# l298_updated_cap.net
KiCad netlist of a schematic drawn in EAGLE
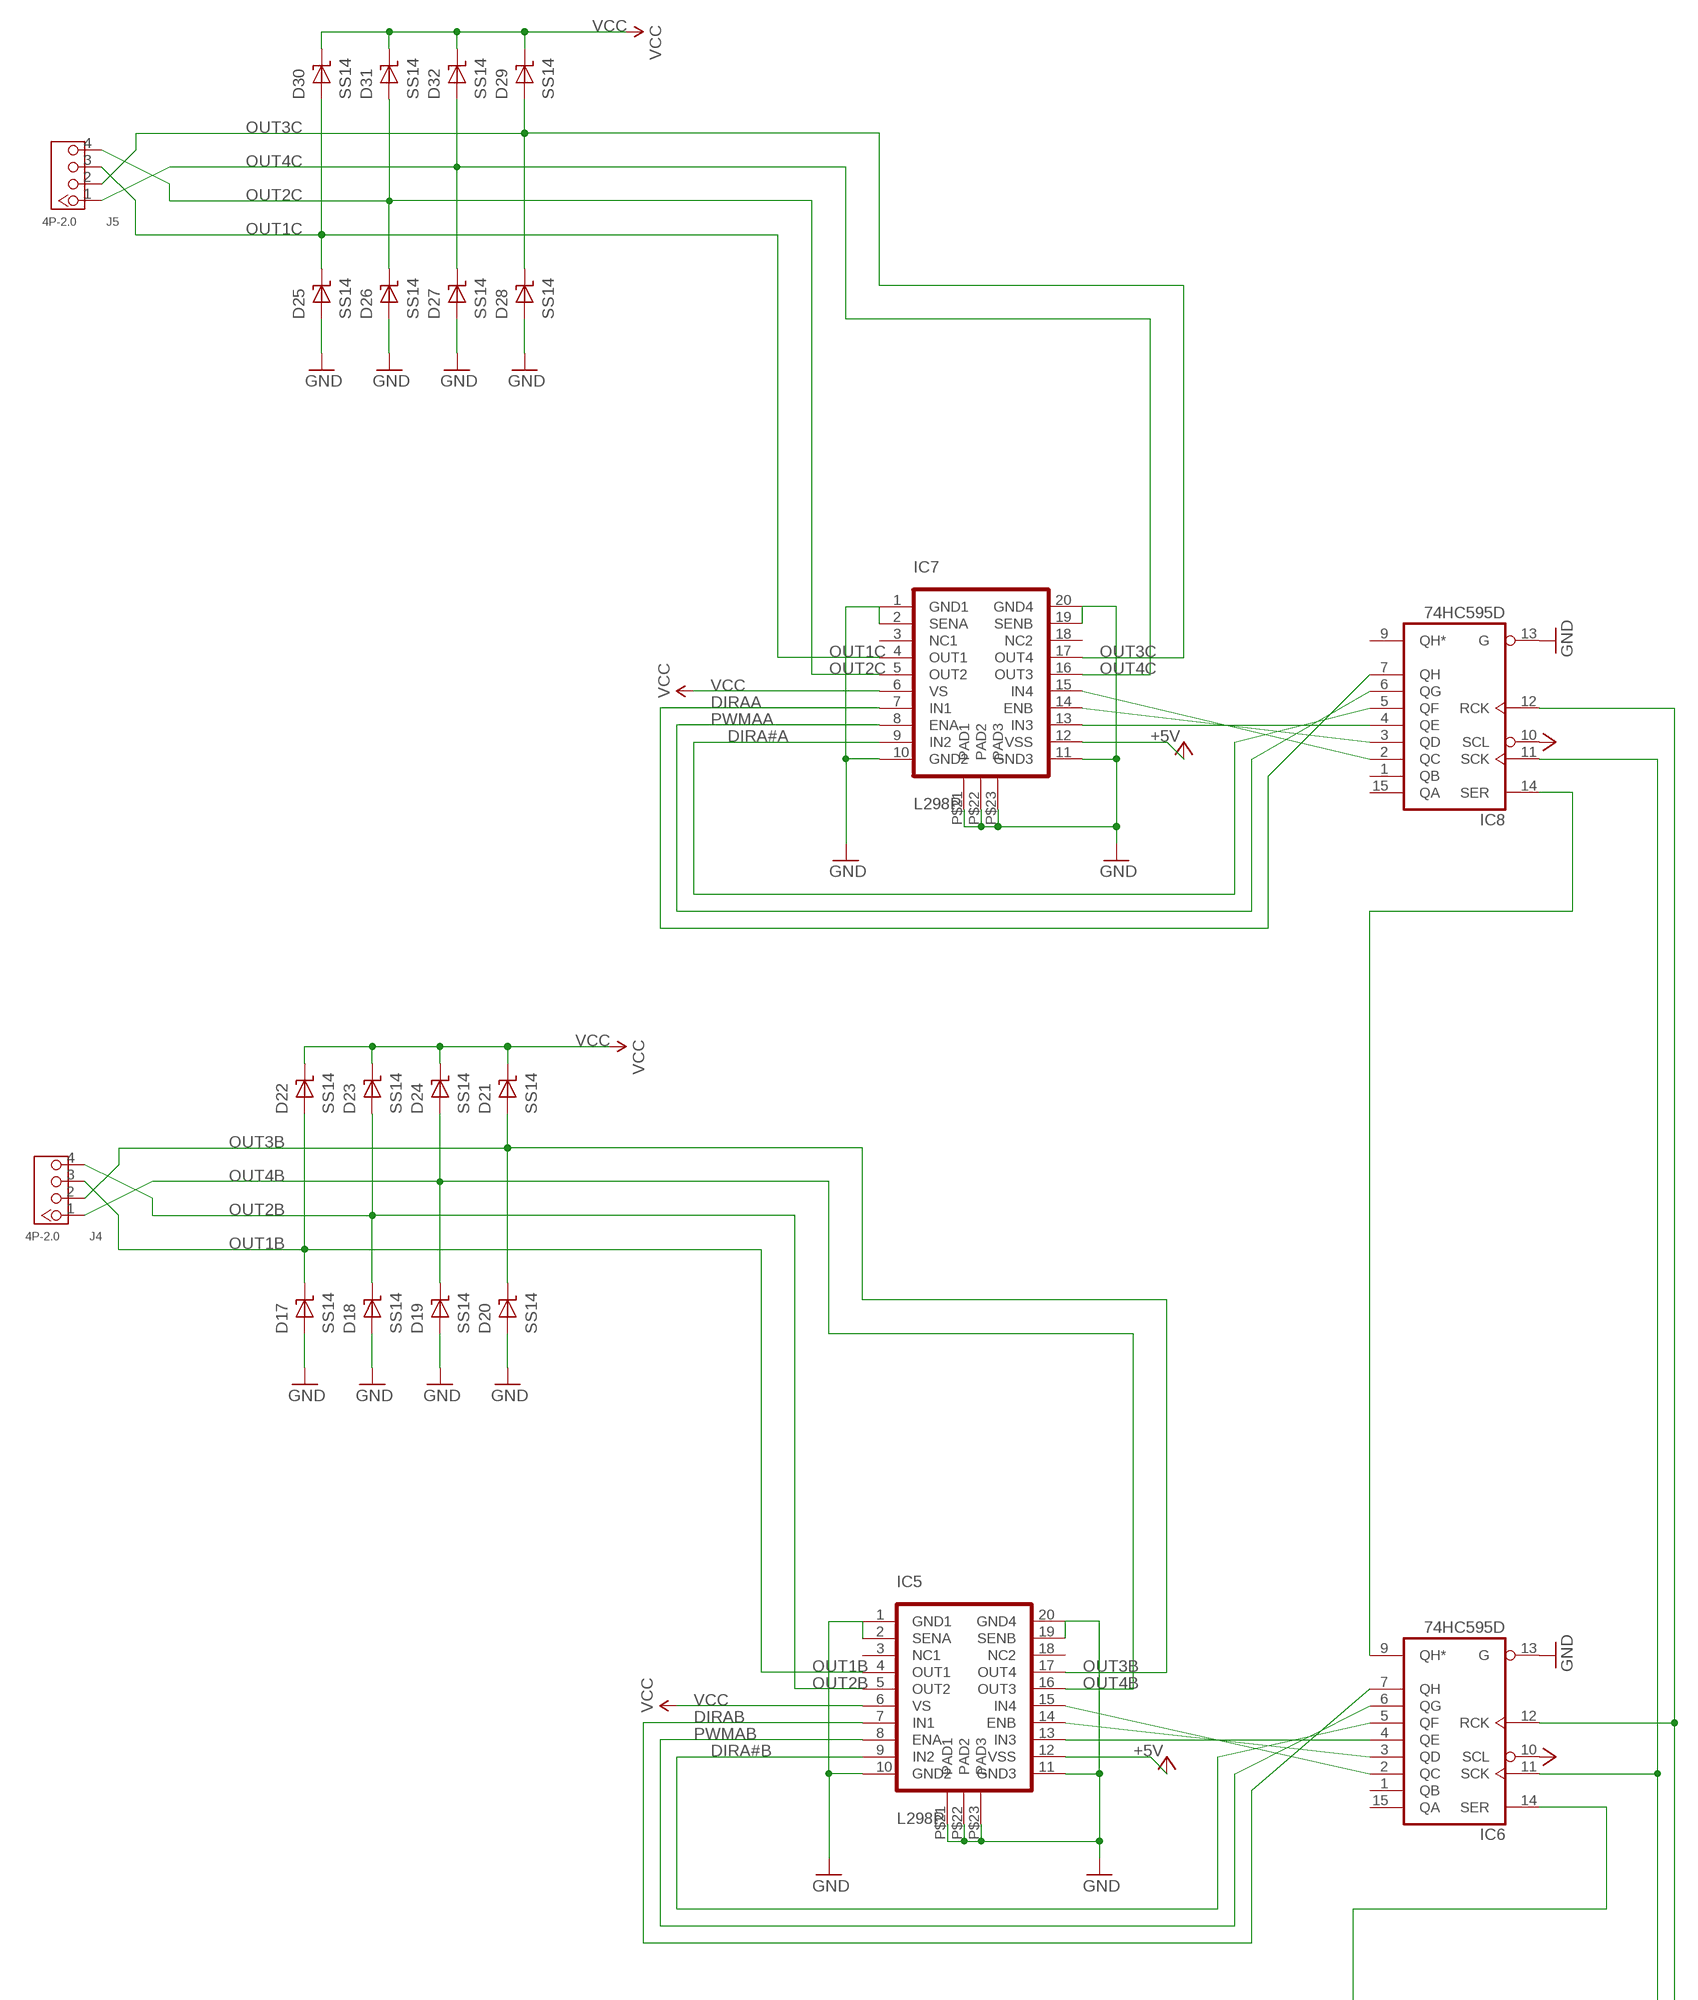
[diagram p0: schematic, sheet 1, part 1 of 2]
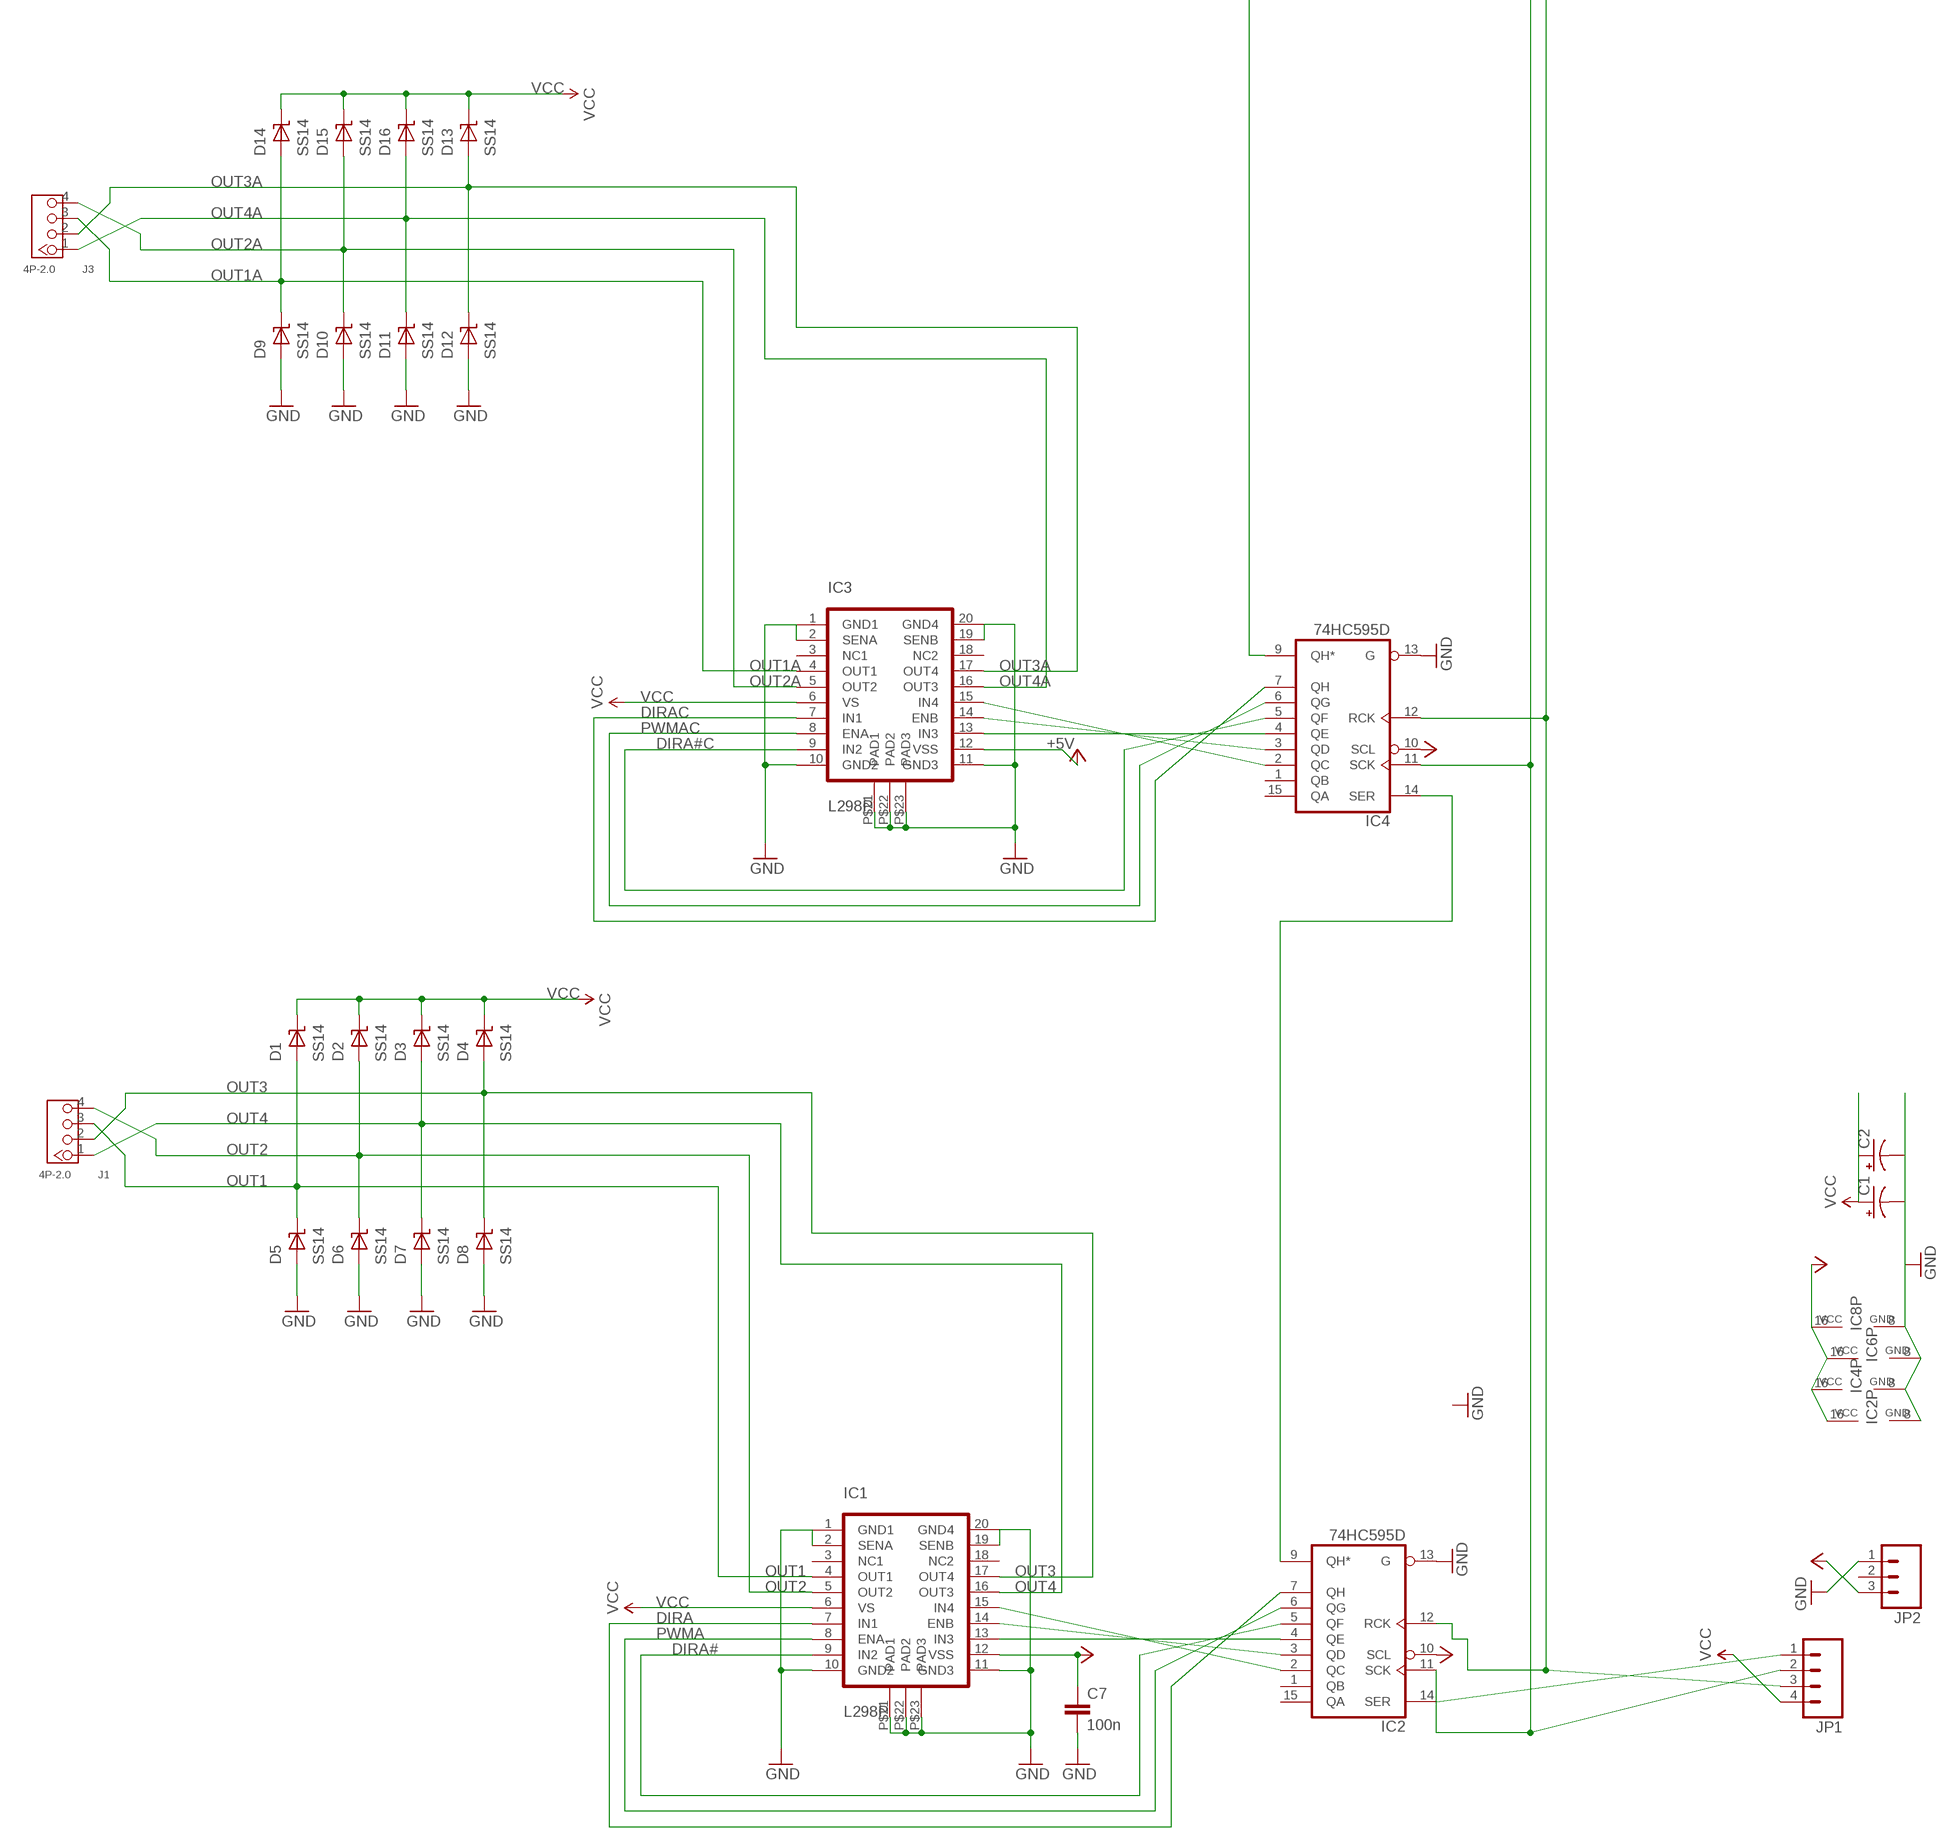
[diagram p1: schematic, sheet 1, part 2 of 2]

(export (version "E")
  (design (tool "Eeschema 10.0.6"))
  (components
    (comp (ref "C1")
      (value "CAP_POL1206")
      (footprint "eagle-import:EIA3216")
      (libsource (lib "eagle-import") (part "CAP_POL1206"))
    )
    (comp (ref "C2")
      (value "CAP_POL3528")
      (footprint "eagle-import:EIA3528")
      (libsource (lib "eagle-import") (part "CAP_POL3528"))
    )
    (comp (ref "C7")
      (value "100n")
      (footprint "eagle-import:C0603-ROUND")
      (libsource (lib "eagle-import") (part "C-EUC0603"))
    )
    (comp (ref "D1")
      (value "SS14")
      (footprint "eagle-import:SMA")
      (libsource (lib "eagle-import") (part "SS14"))
    )
    (comp (ref "D2")
      (value "SS14")
      (footprint "eagle-import:SMA")
      (libsource (lib "eagle-import") (part "SS14"))
    )
    (comp (ref "D3")
      (value "SS14")
      (footprint "eagle-import:SMA")
      (libsource (lib "eagle-import") (part "SS14"))
    )
    (comp (ref "D4")
      (value "SS14")
      (footprint "eagle-import:SMA")
      (libsource (lib "eagle-import") (part "SS14"))
    )
    (comp (ref "D5")
      (value "SS14")
      (footprint "eagle-import:SMA")
      (libsource (lib "eagle-import") (part "SS14"))
    )
    (comp (ref "D6")
      (value "SS14")
      (footprint "eagle-import:SMA")
      (libsource (lib "eagle-import") (part "SS14"))
    )
    (comp (ref "D7")
      (value "SS14")
      (footprint "eagle-import:SMA")
      (libsource (lib "eagle-import") (part "SS14"))
    )
    (comp (ref "D8")
      (value "SS14")
      (footprint "eagle-import:SMA")
      (libsource (lib "eagle-import") (part "SS14"))
    )
    (comp (ref "D9")
      (value "SS14")
      (footprint "eagle-import:SMA")
      (libsource (lib "eagle-import") (part "SS14"))
    )
    (comp (ref "D10")
      (value "SS14")
      (footprint "eagle-import:SMA")
      (libsource (lib "eagle-import") (part "SS14"))
    )
    (comp (ref "D11")
      (value "SS14")
      (footprint "eagle-import:SMA")
      (libsource (lib "eagle-import") (part "SS14"))
    )
    (comp (ref "D12")
      (value "SS14")
      (footprint "eagle-import:SMA")
      (libsource (lib "eagle-import") (part "SS14"))
    )
    (comp (ref "D13")
      (value "SS14")
      (footprint "eagle-import:SMA")
      (libsource (lib "eagle-import") (part "SS14"))
    )
    (comp (ref "D14")
      (value "SS14")
      (footprint "eagle-import:SMA")
      (libsource (lib "eagle-import") (part "SS14"))
    )
    (comp (ref "D15")
      (value "SS14")
      (footprint "eagle-import:SMA")
      (libsource (lib "eagle-import") (part "SS14"))
    )
    (comp (ref "D16")
      (value "SS14")
      (footprint "eagle-import:SMA")
      (libsource (lib "eagle-import") (part "SS14"))
    )
    (comp (ref "D17")
      (value "SS14")
      (footprint "eagle-import:SMA")
      (libsource (lib "eagle-import") (part "SS14"))
    )
    (comp (ref "D18")
      (value "SS14")
      (footprint "eagle-import:SMA")
      (libsource (lib "eagle-import") (part "SS14"))
    )
    (comp (ref "D19")
      (value "SS14")
      (footprint "eagle-import:SMA")
      (libsource (lib "eagle-import") (part "SS14"))
    )
    (comp (ref "D20")
      (value "SS14")
      (footprint "eagle-import:SMA")
      (libsource (lib "eagle-import") (part "SS14"))
    )
    (comp (ref "D21")
      (value "SS14")
      (footprint "eagle-import:SMA")
      (libsource (lib "eagle-import") (part "SS14"))
    )
    (comp (ref "D22")
      (value "SS14")
      (footprint "eagle-import:SMA")
      (libsource (lib "eagle-import") (part "SS14"))
    )
    (comp (ref "D23")
      (value "SS14")
      (footprint "eagle-import:SMA")
      (libsource (lib "eagle-import") (part "SS14"))
    )
    (comp (ref "D24")
      (value "SS14")
      (footprint "eagle-import:SMA")
      (libsource (lib "eagle-import") (part "SS14"))
    )
    (comp (ref "D25")
      (value "SS14")
      (footprint "eagle-import:SMA")
      (libsource (lib "eagle-import") (part "SS14"))
    )
    (comp (ref "D26")
      (value "SS14")
      (footprint "eagle-import:SMA")
      (libsource (lib "eagle-import") (part "SS14"))
    )
    (comp (ref "D27")
      (value "SS14")
      (footprint "eagle-import:SMA")
      (libsource (lib "eagle-import") (part "SS14"))
    )
    (comp (ref "D28")
      (value "SS14")
      (footprint "eagle-import:SMA")
      (libsource (lib "eagle-import") (part "SS14"))
    )
    (comp (ref "D29")
      (value "SS14")
      (footprint "eagle-import:SMA")
      (libsource (lib "eagle-import") (part "SS14"))
    )
    (comp (ref "D30")
      (value "SS14")
      (footprint "eagle-import:SMA")
      (libsource (lib "eagle-import") (part "SS14"))
    )
    (comp (ref "D31")
      (value "SS14")
      (footprint "eagle-import:SMA")
      (libsource (lib "eagle-import") (part "SS14"))
    )
    (comp (ref "D32")
      (value "SS14")
      (footprint "eagle-import:SMA")
      (libsource (lib "eagle-import") (part "SS14"))
    )
    (comp (ref "IC1")
      (value "L298P")
      (footprint "eagle-import:POWER-SO20")
      (libsource (lib "eagle-import") (part "L298P"))
    )
    (comp (ref "IC2")
      (value "74HC595D")
      (footprint "eagle-import:SO16")
      (libsource (lib "eagle-import") (part "74595DHC"))
    )
    (comp (ref "IC3")
      (value "L298P")
      (footprint "eagle-import:POWER-SO20")
      (libsource (lib "eagle-import") (part "L298P"))
    )
    (comp (ref "IC4")
      (value "74HC595D")
      (footprint "eagle-import:SO16")
      (libsource (lib "eagle-import") (part "74595DHC"))
    )
    (comp (ref "IC5")
      (value "L298P")
      (footprint "eagle-import:POWER-SO20")
      (libsource (lib "eagle-import") (part "L298P"))
    )
    (comp (ref "IC6")
      (value "74HC595D")
      (footprint "eagle-import:SO16")
      (libsource (lib "eagle-import") (part "74595DHC"))
    )
    (comp (ref "IC7")
      (value "L298P")
      (footprint "eagle-import:POWER-SO20")
      (libsource (lib "eagle-import") (part "L298P"))
    )
    (comp (ref "IC8")
      (value "74HC595D")
      (footprint "eagle-import:SO16")
      (libsource (lib "eagle-import") (part "74595DHC"))
    )
    (comp (ref "J1")
      (value "4P-2.0")
      (footprint "eagle-import:HW4-2.0")
      (libsource (lib "eagle-import") (part "GROVE-CONNECTOR-DIP(4P-2.0)"))
    )
    (comp (ref "J3")
      (value "4P-2.0")
      (footprint "eagle-import:HW4-2.0")
      (libsource (lib "eagle-import") (part "GROVE-CONNECTOR-DIP(4P-2.0)"))
    )
    (comp (ref "J4")
      (value "4P-2.0")
      (footprint "eagle-import:HW4-2.0")
      (libsource (lib "eagle-import") (part "GROVE-CONNECTOR-DIP(4P-2.0)"))
    )
    (comp (ref "J5")
      (value "4P-2.0")
      (footprint "eagle-import:HW4-2.0")
      (libsource (lib "eagle-import") (part "GROVE-CONNECTOR-DIP(4P-2.0)"))
    )
    (comp (ref "JP1")
      (value "M04PTH")
      (footprint "eagle-import:1X04")
      (libsource (lib "eagle-import") (part "M04PTH"))
    )
    (comp (ref "JP2")
      (value "M03PTH")
      (footprint "eagle-import:1X03")
      (libsource (lib "eagle-import") (part "M03PTH"))
    )
  )
  (nets
    (net (code "1") (name "+5V") (class "Default")
      (node (ref "C7") (pin "1") (pinfunction "1_1") (pintype "passive"))
      (node (ref "IC1") (pin "P$12") (pinfunction "VSS_P$12") (pintype "power_in"))
      (node (ref "IC2") (pin "10") (pinfunction "SCL_10") (pintype "input"))
      (node (ref "IC2") (pin "16") (pinfunction "VCC_16") (pintype "power_in"))
      (node (ref "IC3") (pin "P$12") (pinfunction "VSS_P$12") (pintype "power_in"))
      (node (ref "IC4") (pin "10") (pinfunction "SCL_10") (pintype "input"))
      (node (ref "IC4") (pin "16") (pinfunction "VCC_16") (pintype "power_in"))
      (node (ref "IC5") (pin "P$12") (pinfunction "VSS_P$12") (pintype "power_in"))
      (node (ref "IC6") (pin "10") (pinfunction "SCL_10") (pintype "input"))
      (node (ref "IC6") (pin "16") (pinfunction "VCC_16") (pintype "power_in"))
      (node (ref "IC7") (pin "P$12") (pinfunction "VSS_P$12") (pintype "power_in"))
      (node (ref "IC8") (pin "10") (pinfunction "SCL_10") (pintype "input"))
      (node (ref "IC8") (pin "16") (pinfunction "VCC_16") (pintype "power_in"))
      (node (ref "JP2") (pin "3") (pinfunction "3_3") (pintype "passive"))
    )
    (net (code "2") (name "/DIRA") (class "Default")
      (node (ref "IC1") (pin "P$7") (pinfunction "IN1_P$7") (pintype "input"))
      (node (ref "IC2") (pin "7") (pinfunction "QH_7") (pintype "tri_state"))
    )
    (net (code "3") (name "/DIRA#") (class "Default")
      (node (ref "IC1") (pin "P$9") (pinfunction "IN2_P$9") (pintype "input"))
      (node (ref "IC2") (pin "5") (pinfunction "QF_5") (pintype "tri_state"))
    )
    (net (code "4") (name "/DIRA#A") (class "Default")
      (node (ref "IC7") (pin "P$9") (pinfunction "IN2_P$9") (pintype "input"))
      (node (ref "IC8") (pin "5") (pinfunction "QF_5") (pintype "tri_state"))
    )
    (net (code "5") (name "/DIRA#B") (class "Default")
      (node (ref "IC5") (pin "P$9") (pinfunction "IN2_P$9") (pintype "input"))
      (node (ref "IC6") (pin "5") (pinfunction "QF_5") (pintype "tri_state"))
    )
    (net (code "6") (name "/DIRA#C") (class "Default")
      (node (ref "IC3") (pin "P$9") (pinfunction "IN2_P$9") (pintype "input"))
      (node (ref "IC4") (pin "5") (pinfunction "QF_5") (pintype "tri_state"))
    )
    (net (code "7") (name "/DIRAA") (class "Default")
      (node (ref "IC7") (pin "P$7") (pinfunction "IN1_P$7") (pintype "input"))
      (node (ref "IC8") (pin "7") (pinfunction "QH_7") (pintype "tri_state"))
    )
    (net (code "8") (name "/DIRAB") (class "Default")
      (node (ref "IC5") (pin "P$7") (pinfunction "IN1_P$7") (pintype "input"))
      (node (ref "IC6") (pin "7") (pinfunction "QH_7") (pintype "tri_state"))
    )
    (net (code "9") (name "/DIRAC") (class "Default")
      (node (ref "IC3") (pin "P$7") (pinfunction "IN1_P$7") (pintype "input"))
      (node (ref "IC4") (pin "7") (pinfunction "QH_7") (pintype "tri_state"))
    )
    (net (code "10") (name "/OUT1") (class "Default")
      (node (ref "D1") (pin "P$2") (pinfunction "A_P$2") (pintype "bidirectional"))
      (node (ref "D5") (pin "P$1") (pinfunction "K_P$1") (pintype "bidirectional"))
      (node (ref "IC1") (pin "P$4") (pinfunction "OUT1_P$4") (pintype "output"))
      (node (ref "J1") (pin "3") (pinfunction "3_3") (pintype "bidirectional"))
    )
    (net (code "11") (name "/OUT1A") (class "Default")
      (node (ref "D14") (pin "P$2") (pinfunction "A_P$2") (pintype "bidirectional"))
      (node (ref "D9") (pin "P$1") (pinfunction "K_P$1") (pintype "bidirectional"))
      (node (ref "IC3") (pin "P$4") (pinfunction "OUT1_P$4") (pintype "output"))
      (node (ref "J3") (pin "3") (pinfunction "3_3") (pintype "bidirectional"))
    )
    (net (code "12") (name "/OUT1B") (class "Default")
      (node (ref "D17") (pin "P$1") (pinfunction "K_P$1") (pintype "bidirectional"))
      (node (ref "D22") (pin "P$2") (pinfunction "A_P$2") (pintype "bidirectional"))
      (node (ref "IC5") (pin "P$4") (pinfunction "OUT1_P$4") (pintype "output"))
      (node (ref "J4") (pin "3") (pinfunction "3_3") (pintype "bidirectional"))
    )
    (net (code "13") (name "/OUT1C") (class "Default")
      (node (ref "D25") (pin "P$1") (pinfunction "K_P$1") (pintype "bidirectional"))
      (node (ref "D30") (pin "P$2") (pinfunction "A_P$2") (pintype "bidirectional"))
      (node (ref "IC7") (pin "P$4") (pinfunction "OUT1_P$4") (pintype "output"))
      (node (ref "J5") (pin "3") (pinfunction "3_3") (pintype "bidirectional"))
    )
    (net (code "14") (name "/OUT2") (class "Default")
      (node (ref "D2") (pin "P$2") (pinfunction "A_P$2") (pintype "bidirectional"))
      (node (ref "D6") (pin "P$1") (pinfunction "K_P$1") (pintype "bidirectional"))
      (node (ref "IC1") (pin "P$5") (pinfunction "OUT2_P$5") (pintype "output"))
      (node (ref "J1") (pin "4") (pinfunction "4_4") (pintype "bidirectional"))
    )
    (net (code "15") (name "/OUT2A") (class "Default")
      (node (ref "D10") (pin "P$1") (pinfunction "K_P$1") (pintype "bidirectional"))
      (node (ref "D15") (pin "P$2") (pinfunction "A_P$2") (pintype "bidirectional"))
      (node (ref "IC3") (pin "P$5") (pinfunction "OUT2_P$5") (pintype "output"))
      (node (ref "J3") (pin "4") (pinfunction "4_4") (pintype "bidirectional"))
    )
    (net (code "16") (name "/OUT2B") (class "Default")
      (node (ref "D18") (pin "P$1") (pinfunction "K_P$1") (pintype "bidirectional"))
      (node (ref "D23") (pin "P$2") (pinfunction "A_P$2") (pintype "bidirectional"))
      (node (ref "IC5") (pin "P$5") (pinfunction "OUT2_P$5") (pintype "output"))
      (node (ref "J4") (pin "4") (pinfunction "4_4") (pintype "bidirectional"))
    )
    (net (code "17") (name "/OUT2C") (class "Default")
      (node (ref "D26") (pin "P$1") (pinfunction "K_P$1") (pintype "bidirectional"))
      (node (ref "D31") (pin "P$2") (pinfunction "A_P$2") (pintype "bidirectional"))
      (node (ref "IC7") (pin "P$5") (pinfunction "OUT2_P$5") (pintype "output"))
      (node (ref "J5") (pin "4") (pinfunction "4_4") (pintype "bidirectional"))
    )
    (net (code "18") (name "/OUT3") (class "Default")
      (node (ref "D4") (pin "P$2") (pinfunction "A_P$2") (pintype "bidirectional"))
      (node (ref "D8") (pin "P$1") (pinfunction "K_P$1") (pintype "bidirectional"))
      (node (ref "IC1") (pin "P$17") (pinfunction "OUT4_P$17") (pintype "output"))
      (node (ref "J1") (pin "2") (pinfunction "2_2") (pintype "bidirectional"))
    )
    (net (code "19") (name "/OUT3A") (class "Default")
      (node (ref "D12") (pin "P$1") (pinfunction "K_P$1") (pintype "bidirectional"))
      (node (ref "D13") (pin "P$2") (pinfunction "A_P$2") (pintype "bidirectional"))
      (node (ref "IC3") (pin "P$17") (pinfunction "OUT4_P$17") (pintype "output"))
      (node (ref "J3") (pin "2") (pinfunction "2_2") (pintype "bidirectional"))
    )
    (net (code "20") (name "/OUT3B") (class "Default")
      (node (ref "D20") (pin "P$1") (pinfunction "K_P$1") (pintype "bidirectional"))
      (node (ref "D21") (pin "P$2") (pinfunction "A_P$2") (pintype "bidirectional"))
      (node (ref "IC5") (pin "P$17") (pinfunction "OUT4_P$17") (pintype "output"))
      (node (ref "J4") (pin "2") (pinfunction "2_2") (pintype "bidirectional"))
    )
    (net (code "21") (name "/OUT3C") (class "Default")
      (node (ref "D28") (pin "P$1") (pinfunction "K_P$1") (pintype "bidirectional"))
      (node (ref "D29") (pin "P$2") (pinfunction "A_P$2") (pintype "bidirectional"))
      (node (ref "IC7") (pin "P$17") (pinfunction "OUT4_P$17") (pintype "output"))
      (node (ref "J5") (pin "2") (pinfunction "2_2") (pintype "bidirectional"))
    )
    (net (code "22") (name "/OUT4") (class "Default")
      (node (ref "D3") (pin "P$2") (pinfunction "A_P$2") (pintype "bidirectional"))
      (node (ref "D7") (pin "P$1") (pinfunction "K_P$1") (pintype "bidirectional"))
      (node (ref "IC1") (pin "P$16") (pinfunction "OUT3_P$16") (pintype "output"))
      (node (ref "J1") (pin "1") (pinfunction "1_1") (pintype "bidirectional"))
    )
    (net (code "23") (name "/OUT4A") (class "Default")
      (node (ref "D11") (pin "P$1") (pinfunction "K_P$1") (pintype "bidirectional"))
      (node (ref "D16") (pin "P$2") (pinfunction "A_P$2") (pintype "bidirectional"))
      (node (ref "IC3") (pin "P$16") (pinfunction "OUT3_P$16") (pintype "output"))
      (node (ref "J3") (pin "1") (pinfunction "1_1") (pintype "bidirectional"))
    )
    (net (code "24") (name "/OUT4B") (class "Default")
      (node (ref "D19") (pin "P$1") (pinfunction "K_P$1") (pintype "bidirectional"))
      (node (ref "D24") (pin "P$2") (pinfunction "A_P$2") (pintype "bidirectional"))
      (node (ref "IC5") (pin "P$16") (pinfunction "OUT3_P$16") (pintype "output"))
      (node (ref "J4") (pin "1") (pinfunction "1_1") (pintype "bidirectional"))
    )
    (net (code "25") (name "/OUT4C") (class "Default")
      (node (ref "D27") (pin "P$1") (pinfunction "K_P$1") (pintype "bidirectional"))
      (node (ref "D32") (pin "P$2") (pinfunction "A_P$2") (pintype "bidirectional"))
      (node (ref "IC7") (pin "P$16") (pinfunction "OUT3_P$16") (pintype "output"))
      (node (ref "J5") (pin "1") (pinfunction "1_1") (pintype "bidirectional"))
    )
    (net (code "26") (name "/PWMA") (class "Default")
      (node (ref "IC1") (pin "P$8") (pinfunction "ENA_P$8") (pintype "input"))
      (node (ref "IC2") (pin "6") (pinfunction "QG_6") (pintype "tri_state"))
    )
    (net (code "27") (name "/PWMAA") (class "Default")
      (node (ref "IC7") (pin "P$8") (pinfunction "ENA_P$8") (pintype "input"))
      (node (ref "IC8") (pin "6") (pinfunction "QG_6") (pintype "tri_state"))
    )
    (net (code "28") (name "/PWMAB") (class "Default")
      (node (ref "IC5") (pin "P$8") (pinfunction "ENA_P$8") (pintype "input"))
      (node (ref "IC6") (pin "6") (pinfunction "QG_6") (pintype "tri_state"))
    )
    (net (code "29") (name "/PWMAC") (class "Default")
      (node (ref "IC3") (pin "P$8") (pinfunction "ENA_P$8") (pintype "input"))
      (node (ref "IC4") (pin "6") (pinfunction "QG_6") (pintype "tri_state"))
    )
    (net (code "30") (name "GND") (class "Default")
      (node (ref "C1") (pin "C") (pinfunction "-_C") (pintype "passive"))
      (node (ref "C2") (pin "C") (pinfunction "-_C") (pintype "passive"))
      (node (ref "C7") (pin "2") (pinfunction "2_2") (pintype "passive"))
      (node (ref "D10") (pin "P$2") (pinfunction "A_P$2") (pintype "bidirectional"))
      (node (ref "D11") (pin "P$2") (pinfunction "A_P$2") (pintype "bidirectional"))
      (node (ref "D12") (pin "P$2") (pinfunction "A_P$2") (pintype "bidirectional"))
      (node (ref "D17") (pin "P$2") (pinfunction "A_P$2") (pintype "bidirectional"))
      (node (ref "D18") (pin "P$2") (pinfunction "A_P$2") (pintype "bidirectional"))
      (node (ref "D19") (pin "P$2") (pinfunction "A_P$2") (pintype "bidirectional"))
      (node (ref "D20") (pin "P$2") (pinfunction "A_P$2") (pintype "bidirectional"))
      (node (ref "D25") (pin "P$2") (pinfunction "A_P$2") (pintype "bidirectional"))
      (node (ref "D26") (pin "P$2") (pinfunction "A_P$2") (pintype "bidirectional"))
      (node (ref "D27") (pin "P$2") (pinfunction "A_P$2") (pintype "bidirectional"))
      (node (ref "D28") (pin "P$2") (pinfunction "A_P$2") (pintype "bidirectional"))
      (node (ref "D5") (pin "P$2") (pinfunction "A_P$2") (pintype "bidirectional"))
      (node (ref "D6") (pin "P$2") (pinfunction "A_P$2") (pintype "bidirectional"))
      (node (ref "D7") (pin "P$2") (pinfunction "A_P$2") (pintype "bidirectional"))
      (node (ref "D8") (pin "P$2") (pinfunction "A_P$2") (pintype "bidirectional"))
      (node (ref "D9") (pin "P$2") (pinfunction "A_P$2") (pintype "bidirectional"))
      (node (ref "IC1") (pin "P$1") (pinfunction "GND1_P$1") (pintype "power_in"))
      (node (ref "IC1") (pin "P$10") (pinfunction "GND2_P$10") (pintype "power_in"))
      (node (ref "IC1") (pin "P$11") (pinfunction "GND3_P$11") (pintype "power_in"))
      (node (ref "IC1") (pin "P$19") (pinfunction "SENB_P$19") (pintype "input"))
      (node (ref "IC1") (pin "P$2") (pinfunction "SENA_P$2") (pintype "input"))
      (node (ref "IC1") (pin "P$20") (pinfunction "GND4_P$20") (pintype "power_in"))
      (node (ref "IC1") (pin "P$21") (pinfunction "PAD1_P$21") (pintype "passive"))
      (node (ref "IC1") (pin "P$22") (pinfunction "PAD2_P$22") (pintype "passive"))
      (node (ref "IC1") (pin "P$23") (pinfunction "PAD3_P$23") (pintype "passive"))
      (node (ref "IC2") (pin "13") (pinfunction "G_13") (pintype "input"))
      (node (ref "IC2") (pin "8") (pinfunction "GND_8") (pintype "power_in"))
      (node (ref "IC3") (pin "P$1") (pinfunction "GND1_P$1") (pintype "power_in"))
      (node (ref "IC3") (pin "P$10") (pinfunction "GND2_P$10") (pintype "power_in"))
      (node (ref "IC3") (pin "P$11") (pinfunction "GND3_P$11") (pintype "power_in"))
      (node (ref "IC3") (pin "P$19") (pinfunction "SENB_P$19") (pintype "input"))
      (node (ref "IC3") (pin "P$2") (pinfunction "SENA_P$2") (pintype "input"))
      (node (ref "IC3") (pin "P$20") (pinfunction "GND4_P$20") (pintype "power_in"))
      (node (ref "IC3") (pin "P$21") (pinfunction "PAD1_P$21") (pintype "passive"))
      (node (ref "IC3") (pin "P$22") (pinfunction "PAD2_P$22") (pintype "passive"))
      (node (ref "IC3") (pin "P$23") (pinfunction "PAD3_P$23") (pintype "passive"))
      (node (ref "IC4") (pin "13") (pinfunction "G_13") (pintype "input"))
      (node (ref "IC4") (pin "8") (pinfunction "GND_8") (pintype "power_in"))
      (node (ref "IC5") (pin "P$1") (pinfunction "GND1_P$1") (pintype "power_in"))
      (node (ref "IC5") (pin "P$10") (pinfunction "GND2_P$10") (pintype "power_in"))
      (node (ref "IC5") (pin "P$11") (pinfunction "GND3_P$11") (pintype "power_in"))
      (node (ref "IC5") (pin "P$19") (pinfunction "SENB_P$19") (pintype "input"))
      (node (ref "IC5") (pin "P$2") (pinfunction "SENA_P$2") (pintype "input"))
      (node (ref "IC5") (pin "P$20") (pinfunction "GND4_P$20") (pintype "power_in"))
      (node (ref "IC5") (pin "P$21") (pinfunction "PAD1_P$21") (pintype "passive"))
      (node (ref "IC5") (pin "P$22") (pinfunction "PAD2_P$22") (pintype "passive"))
      (node (ref "IC5") (pin "P$23") (pinfunction "PAD3_P$23") (pintype "passive"))
      (node (ref "IC6") (pin "13") (pinfunction "G_13") (pintype "input"))
      (node (ref "IC6") (pin "8") (pinfunction "GND_8") (pintype "power_in"))
      (node (ref "IC7") (pin "P$1") (pinfunction "GND1_P$1") (pintype "power_in"))
      (node (ref "IC7") (pin "P$10") (pinfunction "GND2_P$10") (pintype "power_in"))
      (node (ref "IC7") (pin "P$11") (pinfunction "GND3_P$11") (pintype "power_in"))
      (node (ref "IC7") (pin "P$19") (pinfunction "SENB_P$19") (pintype "input"))
      (node (ref "IC7") (pin "P$2") (pinfunction "SENA_P$2") (pintype "input"))
      (node (ref "IC7") (pin "P$20") (pinfunction "GND4_P$20") (pintype "power_in"))
      (node (ref "IC7") (pin "P$21") (pinfunction "PAD1_P$21") (pintype "passive"))
      (node (ref "IC7") (pin "P$22") (pinfunction "PAD2_P$22") (pintype "passive"))
      (node (ref "IC7") (pin "P$23") (pinfunction "PAD3_P$23") (pintype "passive"))
      (node (ref "IC8") (pin "13") (pinfunction "G_13") (pintype "input"))
      (node (ref "IC8") (pin "8") (pinfunction "GND_8") (pintype "power_in"))
      (node (ref "JP2") (pin "1") (pinfunction "1_1") (pintype "passive"))
    )
    (net (code "31") (name "Net-(IC1-ENB)") (class "Default")
      (node (ref "IC1") (pin "P$14") (pinfunction "ENB_P$14") (pintype "input"))
      (node (ref "IC2") (pin "3") (pinfunction "QD_3") (pintype "tri_state"))
    )
    (net (code "32") (name "Net-(IC1-IN3)") (class "Default")
      (node (ref "IC1") (pin "P$13") (pinfunction "IN3_P$13") (pintype "input"))
      (node (ref "IC2") (pin "4") (pinfunction "QE_4") (pintype "tri_state"))
    )
    (net (code "33") (name "Net-(IC1-IN4)") (class "Default")
      (node (ref "IC1") (pin "P$15") (pinfunction "IN4_P$15") (pintype "input"))
      (node (ref "IC2") (pin "2") (pinfunction "QC_2") (pintype "tri_state"))
    )
    (net (code "34") (name "Net-(IC2A-QH*)") (class "Default")
      (node (ref "IC2") (pin "9") (pinfunction "QH*_9") (pintype "tri_state"))
      (node (ref "IC4") (pin "14") (pinfunction "SER_14") (pintype "input"))
    )
    (net (code "35") (name "Net-(IC2A-RCK)") (class "Default")
      (node (ref "IC2") (pin "12") (pinfunction "RCK_12") (pintype "input"))
      (node (ref "IC4") (pin "12") (pinfunction "RCK_12") (pintype "input"))
      (node (ref "IC6") (pin "12") (pinfunction "RCK_12") (pintype "input"))
      (node (ref "IC8") (pin "12") (pinfunction "RCK_12") (pintype "input"))
      (node (ref "JP1") (pin "3") (pinfunction "3_3") (pintype "passive"))
    )
    (net (code "36") (name "Net-(IC2A-SCK)") (class "Default")
      (node (ref "IC2") (pin "11") (pinfunction "SCK_11") (pintype "input"))
      (node (ref "IC4") (pin "11") (pinfunction "SCK_11") (pintype "input"))
      (node (ref "IC6") (pin "11") (pinfunction "SCK_11") (pintype "input"))
      (node (ref "IC8") (pin "11") (pinfunction "SCK_11") (pintype "input"))
      (node (ref "JP1") (pin "2") (pinfunction "2_2") (pintype "passive"))
    )
    (net (code "37") (name "Net-(IC2A-SER)") (class "Default")
      (node (ref "IC2") (pin "14") (pinfunction "SER_14") (pintype "input"))
      (node (ref "JP1") (pin "1") (pinfunction "1_1") (pintype "passive"))
    )
    (net (code "38") (name "Net-(IC3-ENB)") (class "Default")
      (node (ref "IC3") (pin "P$14") (pinfunction "ENB_P$14") (pintype "input"))
      (node (ref "IC4") (pin "3") (pinfunction "QD_3") (pintype "tri_state"))
    )
    (net (code "39") (name "Net-(IC3-IN3)") (class "Default")
      (node (ref "IC3") (pin "P$13") (pinfunction "IN3_P$13") (pintype "input"))
      (node (ref "IC4") (pin "4") (pinfunction "QE_4") (pintype "tri_state"))
    )
    (net (code "40") (name "Net-(IC3-IN4)") (class "Default")
      (node (ref "IC3") (pin "P$15") (pinfunction "IN4_P$15") (pintype "input"))
      (node (ref "IC4") (pin "2") (pinfunction "QC_2") (pintype "tri_state"))
    )
    (net (code "41") (name "Net-(IC4A-QH*)") (class "Default")
      (node (ref "IC4") (pin "9") (pinfunction "QH*_9") (pintype "tri_state"))
      (node (ref "IC6") (pin "14") (pinfunction "SER_14") (pintype "input"))
    )
    (net (code "42") (name "Net-(IC5-ENB)") (class "Default")
      (node (ref "IC5") (pin "P$14") (pinfunction "ENB_P$14") (pintype "input"))
      (node (ref "IC6") (pin "3") (pinfunction "QD_3") (pintype "tri_state"))
    )
    (net (code "43") (name "Net-(IC5-IN3)") (class "Default")
      (node (ref "IC5") (pin "P$13") (pinfunction "IN3_P$13") (pintype "input"))
      (node (ref "IC6") (pin "4") (pinfunction "QE_4") (pintype "tri_state"))
    )
    (net (code "44") (name "Net-(IC5-IN4)") (class "Default")
      (node (ref "IC5") (pin "P$15") (pinfunction "IN4_P$15") (pintype "input"))
      (node (ref "IC6") (pin "2") (pinfunction "QC_2") (pintype "tri_state"))
    )
    (net (code "45") (name "Net-(IC6A-QH*)") (class "Default")
      (node (ref "IC6") (pin "9") (pinfunction "QH*_9") (pintype "tri_state"))
      (node (ref "IC8") (pin "14") (pinfunction "SER_14") (pintype "input"))
    )
    (net (code "46") (name "Net-(IC7-ENB)") (class "Default")
      (node (ref "IC7") (pin "P$14") (pinfunction "ENB_P$14") (pintype "input"))
      (node (ref "IC8") (pin "3") (pinfunction "QD_3") (pintype "tri_state"))
    )
    (net (code "47") (name "Net-(IC7-IN3)") (class "Default")
      (node (ref "IC7") (pin "P$13") (pinfunction "IN3_P$13") (pintype "input"))
      (node (ref "IC8") (pin "4") (pinfunction "QE_4") (pintype "tri_state"))
    )
    (net (code "48") (name "Net-(IC7-IN4)") (class "Default")
      (node (ref "IC7") (pin "P$15") (pinfunction "IN4_P$15") (pintype "input"))
      (node (ref "IC8") (pin "2") (pinfunction "QC_2") (pintype "tri_state"))
    )
    (net (code "49") (name "VCC") (class "Default")
      (node (ref "C1") (pin "A") (pinfunction "+_A") (pintype "passive"))
      (node (ref "C2") (pin "A") (pinfunction "+_A") (pintype "passive"))
      (node (ref "D1") (pin "P$1") (pinfunction "K_P$1") (pintype "bidirectional"))
      (node (ref "D13") (pin "P$1") (pinfunction "K_P$1") (pintype "bidirectional"))
      (node (ref "D14") (pin "P$1") (pinfunction "K_P$1") (pintype "bidirectional"))
      (node (ref "D15") (pin "P$1") (pinfunction "K_P$1") (pintype "bidirectional"))
      (node (ref "D16") (pin "P$1") (pinfunction "K_P$1") (pintype "bidirectional"))
      (node (ref "D2") (pin "P$1") (pinfunction "K_P$1") (pintype "bidirectional"))
      (node (ref "D21") (pin "P$1") (pinfunction "K_P$1") (pintype "bidirectional"))
      (node (ref "D22") (pin "P$1") (pinfunction "K_P$1") (pintype "bidirectional"))
      (node (ref "D23") (pin "P$1") (pinfunction "K_P$1") (pintype "bidirectional"))
      (node (ref "D24") (pin "P$1") (pinfunction "K_P$1") (pintype "bidirectional"))
      (node (ref "D29") (pin "P$1") (pinfunction "K_P$1") (pintype "bidirectional"))
      (node (ref "D3") (pin "P$1") (pinfunction "K_P$1") (pintype "bidirectional"))
      (node (ref "D30") (pin "P$1") (pinfunction "K_P$1") (pintype "bidirectional"))
      (node (ref "D31") (pin "P$1") (pinfunction "K_P$1") (pintype "bidirectional"))
      (node (ref "D32") (pin "P$1") (pinfunction "K_P$1") (pintype "bidirectional"))
      (node (ref "D4") (pin "P$1") (pinfunction "K_P$1") (pintype "bidirectional"))
      (node (ref "IC1") (pin "P$6") (pinfunction "VS_P$6") (pintype "power_in"))
      (node (ref "IC3") (pin "P$6") (pinfunction "VS_P$6") (pintype "power_in"))
      (node (ref "IC5") (pin "P$6") (pinfunction "VS_P$6") (pintype "power_in"))
      (node (ref "IC7") (pin "P$6") (pinfunction "VS_P$6") (pintype "power_in"))
      (node (ref "JP1") (pin "4") (pinfunction "4_4") (pintype "passive"))
    )
    (net (code "50") (name "unconnected-(IC1-NC1-PadP$3)") (class "Default")
      (node (ref "IC1") (pin "P$3") (pinfunction "NC1_P$3") (pintype "no_connect"))
    )
    (net (code "51") (name "unconnected-(IC1-NC2-PadP$18)") (class "Default")
      (node (ref "IC1") (pin "P$18") (pinfunction "NC2_P$18") (pintype "no_connect"))
    )
    (net (code "52") (name "unconnected-(IC2A-QA-Pad15)") (class "Default")
      (node (ref "IC2") (pin "15") (pinfunction "QA_15") (pintype "tri_state"))
    )
    (net (code "53") (name "unconnected-(IC2A-QB-Pad1)") (class "Default")
      (node (ref "IC2") (pin "1") (pinfunction "QB_1") (pintype "tri_state"))
    )
    (net (code "54") (name "unconnected-(IC3-NC1-PadP$3)") (class "Default")
      (node (ref "IC3") (pin "P$3") (pinfunction "NC1_P$3") (pintype "no_connect"))
    )
    (net (code "55") (name "unconnected-(IC3-NC2-PadP$18)") (class "Default")
      (node (ref "IC3") (pin "P$18") (pinfunction "NC2_P$18") (pintype "no_connect"))
    )
    (net (code "56") (name "unconnected-(IC4A-QA-Pad15)") (class "Default")
      (node (ref "IC4") (pin "15") (pinfunction "QA_15") (pintype "tri_state"))
    )
    (net (code "57") (name "unconnected-(IC4A-QB-Pad1)") (class "Default")
      (node (ref "IC4") (pin "1") (pinfunction "QB_1") (pintype "tri_state"))
    )
    (net (code "58") (name "unconnected-(IC5-NC1-PadP$3)") (class "Default")
      (node (ref "IC5") (pin "P$3") (pinfunction "NC1_P$3") (pintype "no_connect"))
    )
    (net (code "59") (name "unconnected-(IC5-NC2-PadP$18)") (class "Default")
      (node (ref "IC5") (pin "P$18") (pinfunction "NC2_P$18") (pintype "no_connect"))
    )
    (net (code "60") (name "unconnected-(IC6A-QA-Pad15)") (class "Default")
      (node (ref "IC6") (pin "15") (pinfunction "QA_15") (pintype "tri_state"))
    )
    (net (code "61") (name "unconnected-(IC6A-QB-Pad1)") (class "Default")
      (node (ref "IC6") (pin "1") (pinfunction "QB_1") (pintype "tri_state"))
    )
    (net (code "62") (name "unconnected-(IC7-NC1-PadP$3)") (class "Default")
      (node (ref "IC7") (pin "P$3") (pinfunction "NC1_P$3") (pintype "no_connect"))
    )
    (net (code "63") (name "unconnected-(IC7-NC2-PadP$18)") (class "Default")
      (node (ref "IC7") (pin "P$18") (pinfunction "NC2_P$18") (pintype "no_connect"))
    )
    (net (code "64") (name "unconnected-(IC8A-QA-Pad15)") (class "Default")
      (node (ref "IC8") (pin "15") (pinfunction "QA_15") (pintype "tri_state"))
    )
    (net (code "65") (name "unconnected-(IC8A-QB-Pad1)") (class "Default")
      (node (ref "IC8") (pin "1") (pinfunction "QB_1") (pintype "tri_state"))
    )
    (net (code "66") (name "unconnected-(IC8A-QH*-Pad9)") (class "Default")
      (node (ref "IC8") (pin "9") (pinfunction "QH*_9") (pintype "tri_state"))
    )
    (net (code "67") (name "unconnected-(JP2-Pad2)") (class "Default")
      (node (ref "JP2") (pin "2") (pinfunction "2_2") (pintype "passive"))
    )
  )
)
